# Wedding_Centerpiece_Controller_V1_1.net
KiCad netlist of a schematic drawn in EAGLE
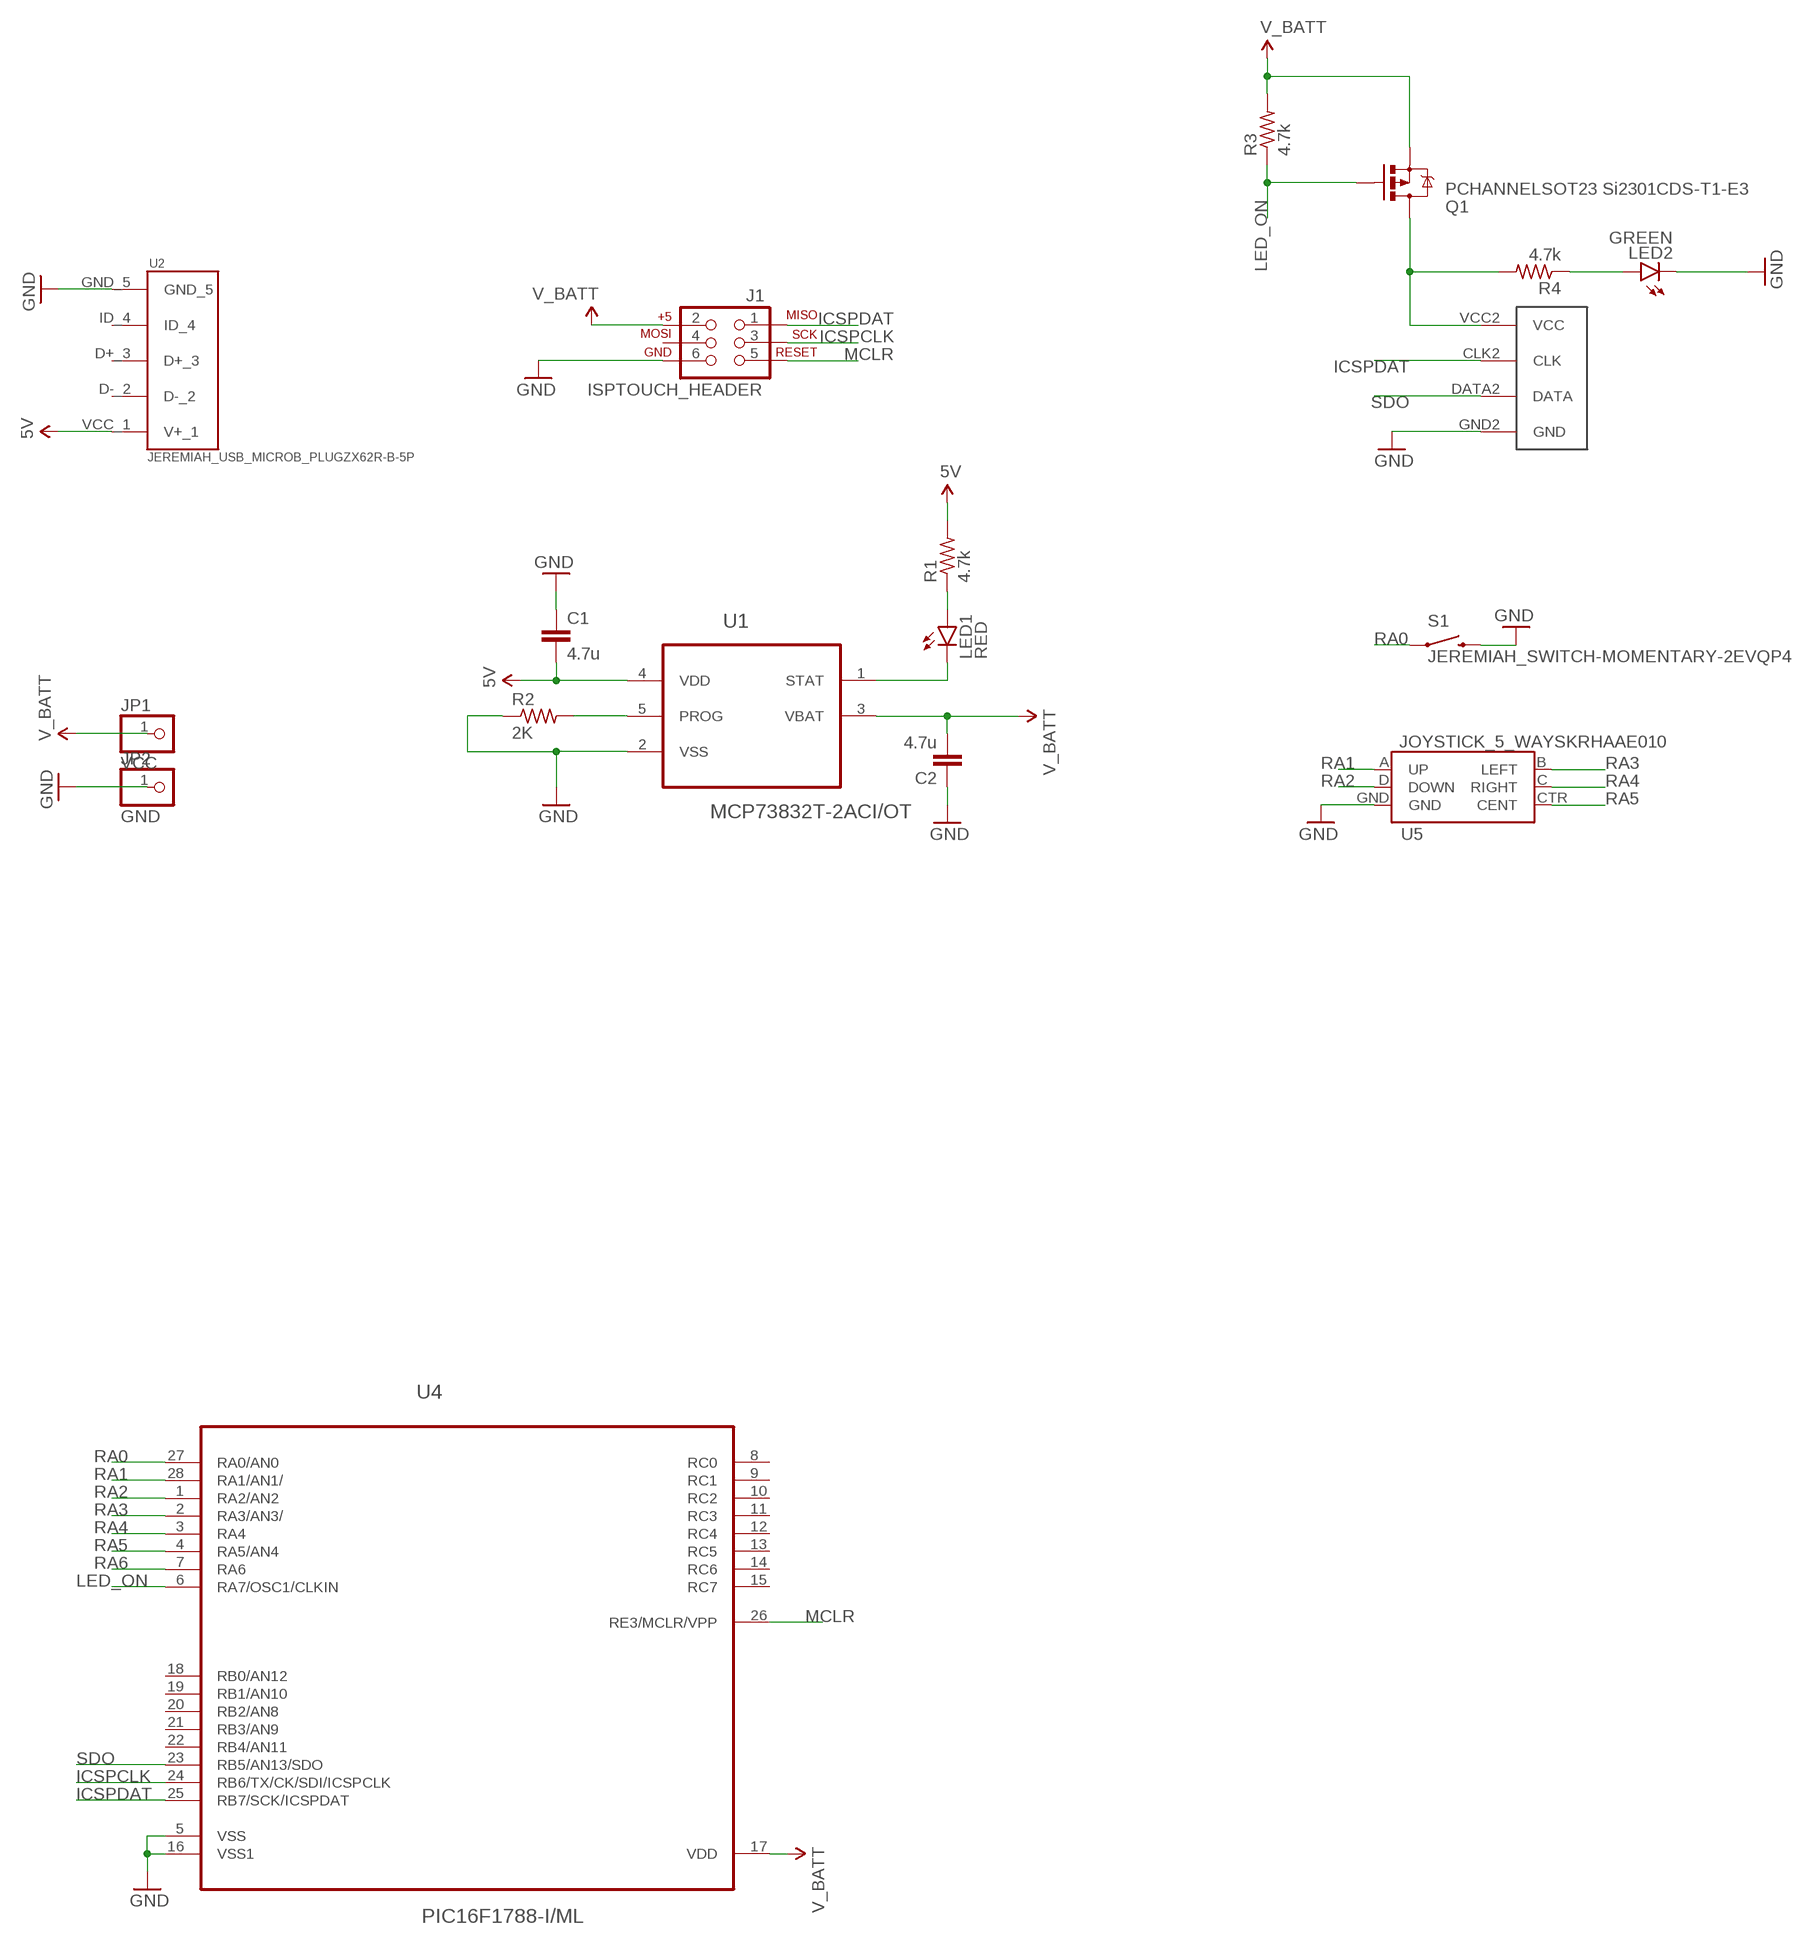
[diagram p0: schematic, sheet 1]

(export (version "E")
  (design (tool "Eeschema 10.0.6"))
  (components
    (comp (ref "C1")
      (value "4.7u")
      (footprint "eagle-import:0402-CAP")
      (libsource (lib "eagle-import") (part "CAP0402-CAP"))
    )
    (comp (ref "C2")
      (value "4.7u")
      (footprint "eagle-import:0402-CAP")
      (libsource (lib "eagle-import") (part "CAP0402-CAP"))
    )
    (comp (ref "J1")
      (value "ISPTOUCH_HEADER")
      (footprint "eagle-import:AVX_9188_6-WAY_MATING_GUIDE")
      (libsource (lib "eagle-import") (part "ISPTOUCH_HEADER"))
    )
    (comp (ref "JP1")
      (value "VCC")
      (footprint "eagle-import:1X01")
      (libsource (lib "eagle-import") (part "PINHD-1X1"))
    )
    (comp (ref "JP2")
      (value "GND")
      (footprint "eagle-import:1X01")
      (libsource (lib "eagle-import") (part "PINHD-1X1"))
    )
    (comp (ref "LED1")
      (value "RED")
      (footprint "eagle-import:LED-0603")
      (libsource (lib "eagle-import") (part "LED0603"))
    )
    (comp (ref "LED2")
      (value "GREEN")
      (footprint "eagle-import:LED-0603")
      (libsource (lib "eagle-import") (part "LED0603"))
    )
    (comp (ref "Q1")
      (value "PCHANNELSOT23 Si2301CDS-T1-E3")
      (footprint "eagle-import:JEREMIAH_SOT23")
      (libsource (lib "eagle-import") (part "JEREMIAH_MOSFET-PCHANNELSOT23"))
    )
    (comp (ref "R1")
      (value "4.7k")
      (footprint "eagle-import:R0402")
      (libsource (lib "eagle-import") (part "R-US_R0402"))
    )
    (comp (ref "R2")
      (value "2K")
      (footprint "eagle-import:R0402")
      (libsource (lib "eagle-import") (part "R-US_R0402"))
    )
    (comp (ref "R3")
      (value "4.7k")
      (footprint "eagle-import:R0402")
      (libsource (lib "eagle-import") (part "R-US_R0402"))
    )
    (comp (ref "R4")
      (value "4.7k")
      (footprint "eagle-import:R0402")
      (libsource (lib "eagle-import") (part "R-US_R0402"))
    )
    (comp (ref "S1")
      (value "JEREMIAH_SWITCH-MOMENTARY-2EVQP4")
      (footprint "eagle-import:JEREMIAH_EVQP4_SWITCH")
      (libsource (lib "eagle-import") (part "JEREMIAH_SWITCH-MOMENTARY-2EVQP4"))
    )
    (comp (ref "U1")
      (value "MCP73832T-2ACI/OT")
      (footprint "eagle-import:SOT95P280X145-5N")
      (libsource (lib "eagle-import") (part "MCP73832T-2ACI/OT"))
    )
    (comp (ref "U2")
      (value "JEREMIAH_USB_MICROB_PLUGZX62R-B-5P")
      (footprint "eagle-import:JEREMIAH_USB_MICRO_ZX62R-B-5P")
      (libsource (lib "eagle-import") (part "JEREMIAH_USB_MICROB_PLUGZX62R-B-5P"))
    )
    (comp (ref "U3")
      (value "JEREMIAH_LED_STRIP_WS2801CLENLED_2L_BEGIN")
      (footprint "eagle-import:JEREMIAH_LED_STRIP_WS2801_CLENLED_2L_BEGIN")
      (libsource (lib "eagle-import") (part "JEREMIAH_LED_STRIP_WS2801CLENLED_2L_BEGIN"))
    )
    (comp (ref "U4")
      (value "PIC16F1788-I/ML")
      (footprint "eagle-import:QFN65P600X600X100-29N")
      (libsource (lib "eagle-import") (part "PIC16F1788-I/ML"))
    )
    (comp (ref "U5")
      (value "JOYSTICK_5_WAYSKRHAAE010")
      (footprint "eagle-import:ALPS_SKRHAAE010")
      (libsource (lib "eagle-import") (part "JOYSTICK_5_WAYSKRHAAE010"))
    )
  )
  (nets
    (net (code "1") (name "/ICSPCLK") (class "Default")
      (node (ref "J1") (pin "3") (pinfunction "3_3") (pintype "passive"))
      (node (ref "U4") (pin "24") (pinfunction "RB6/TX/CK/SDI/ICSPCLK_24") (pintype "bidirectional"))
    )
    (net (code "2") (name "/ICSPDAT") (class "Default")
      (node (ref "J1") (pin "1") (pinfunction "1_1") (pintype "passive"))
      (node (ref "U3") (pin "CLK2") (pinfunction "CLK_CLK2") (pintype "bidirectional"))
      (node (ref "U4") (pin "25") (pinfunction "RB7/SCK/ICSPDAT_25") (pintype "bidirectional"))
    )
    (net (code "3") (name "/LED_ON") (class "Default")
      (node (ref "Q1") (pin "1") (pinfunction "G_1") (pintype "passive"))
      (node (ref "R3") (pin "1") (pinfunction "1_1") (pintype "passive"))
      (node (ref "U4") (pin "6") (pinfunction "RA7/OSC1/CLKIN_6") (pintype "bidirectional"))
    )
    (net (code "4") (name "/MCLR") (class "Default")
      (node (ref "J1") (pin "5") (pinfunction "5_5") (pintype "passive"))
      (node (ref "U4") (pin "26") (pinfunction "RE3/MCLR/VPP_26") (pintype "bidirectional"))
    )
    (net (code "5") (name "/RA0") (class "Default")
      (node (ref "S1") (pin "1") (pinfunction "1_1") (pintype "passive"))
      (node (ref "U4") (pin "27") (pinfunction "RA0/AN0_27") (pintype "bidirectional"))
    )
    (net (code "6") (name "/RA1") (class "Default")
      (node (ref "U4") (pin "28") (pinfunction "RA1/AN1/_28") (pintype "bidirectional"))
      (node (ref "U5") (pin "A") (pinfunction "UP_A") (pintype "bidirectional"))
    )
    (net (code "7") (name "/RA2") (class "Default")
      (node (ref "U4") (pin "1") (pinfunction "RA2/AN2_1") (pintype "bidirectional"))
      (node (ref "U5") (pin "D") (pinfunction "DOWN_D") (pintype "bidirectional"))
    )
    (net (code "8") (name "/RA3") (class "Default")
      (node (ref "U4") (pin "2") (pinfunction "RA3/AN3/_2") (pintype "bidirectional"))
      (node (ref "U5") (pin "B") (pinfunction "LEFT_B") (pintype "bidirectional"))
    )
    (net (code "9") (name "/RA4") (class "Default")
      (node (ref "U4") (pin "3") (pinfunction "RA4_3") (pintype "bidirectional"))
      (node (ref "U5") (pin "C") (pinfunction "RIGHT_C") (pintype "bidirectional"))
    )
    (net (code "10") (name "/RA5") (class "Default")
      (node (ref "U4") (pin "4") (pinfunction "RA5/AN4_4") (pintype "input"))
      (node (ref "U5") (pin "CTR") (pinfunction "CENT_CTR") (pintype "bidirectional"))
    )
    (net (code "11") (name "/RA6") (class "Default")
      (node (ref "U4") (pin "7") (pinfunction "RA6_7") (pintype "bidirectional"))
    )
    (net (code "12") (name "/SDO") (class "Default")
      (node (ref "U3") (pin "DATA2") (pinfunction "DATA_DATA2") (pintype "bidirectional"))
      (node (ref "U4") (pin "23") (pinfunction "RB5/AN13/SDO_23") (pintype "bidirectional"))
    )
    (net (code "13") (name "5V") (class "Default")
      (node (ref "C1") (pin "2") (pinfunction "2_2") (pintype "passive"))
      (node (ref "R1") (pin "2") (pinfunction "2_2") (pintype "passive"))
      (node (ref "U1") (pin "4") (pinfunction "VDD_4") (pintype "power_in"))
      (node (ref "U2") (pin "VCC_1") (pinfunction "V+_1_VCC_1") (pintype "bidirectional"))
    )
    (net (code "14") (name "GND") (class "Default")
      (node (ref "C1") (pin "1") (pinfunction "1_1") (pintype "passive"))
      (node (ref "C2") (pin "1") (pinfunction "1_1") (pintype "passive"))
      (node (ref "J1") (pin "6") (pinfunction "6_6") (pintype "passive"))
      (node (ref "JP2") (pin "1") (pinfunction "1_1") (pintype "passive"))
      (node (ref "LED2") (pin "C") (pinfunction "C_C") (pintype "passive"))
      (node (ref "R2") (pin "1") (pinfunction "1_1") (pintype "passive"))
      (node (ref "S1") (pin "2") (pinfunction "2_2") (pintype "passive"))
      (node (ref "U1") (pin "2") (pinfunction "VSS_2") (pintype "power_in"))
      (node (ref "U2") (pin "GND_5") (pinfunction "GND_5_GND_5") (pintype "bidirectional"))
      (node (ref "U3") (pin "GND2") (pinfunction "GND_GND2") (pintype "bidirectional"))
      (node (ref "U4") (pin "16") (pinfunction "VSS1_16") (pintype "power_in"))
      (node (ref "U4") (pin "5") (pinfunction "VSS_5") (pintype "power_in"))
      (node (ref "U5") (pin "GND") (pinfunction "GND_GND") (pintype "bidirectional"))
    )
    (net (code "15") (name "Net-(LED1-PadA)") (class "Default")
      (node (ref "LED1") (pin "A") (pinfunction "A_A") (pintype "passive"))
      (node (ref "R1") (pin "1") (pinfunction "1_1") (pintype "passive"))
    )
    (net (code "16") (name "Net-(LED2-PadA)") (class "Default")
      (node (ref "LED2") (pin "A") (pinfunction "A_A") (pintype "passive"))
      (node (ref "R4") (pin "1") (pinfunction "1_1") (pintype "passive"))
    )
    (net (code "17") (name "Net-(Q1-D)") (class "Default")
      (node (ref "Q1") (pin "3") (pinfunction "D_3") (pintype "passive"))
      (node (ref "R4") (pin "2") (pinfunction "2_2") (pintype "passive"))
      (node (ref "U3") (pin "VCC2") (pinfunction "VCC_VCC2") (pintype "bidirectional"))
    )
    (net (code "18") (name "Net-(U1-PROG)") (class "Default")
      (node (ref "R2") (pin "2") (pinfunction "2_2") (pintype "passive"))
      (node (ref "U1") (pin "5") (pinfunction "PROG_5") (pintype "input"))
    )
    (net (code "19") (name "Net-(U1-STAT)") (class "Default")
      (node (ref "LED1") (pin "C") (pinfunction "C_C") (pintype "passive"))
      (node (ref "U1") (pin "1") (pinfunction "STAT_1") (pintype "output"))
    )
    (net (code "20") (name "V_BATT") (class "Default")
      (node (ref "C2") (pin "2") (pinfunction "2_2") (pintype "passive"))
      (node (ref "J1") (pin "2") (pinfunction "2_2") (pintype "passive"))
      (node (ref "JP1") (pin "1") (pinfunction "1_1") (pintype "passive"))
      (node (ref "Q1") (pin "2") (pinfunction "S_2") (pintype "passive"))
      (node (ref "R3") (pin "2") (pinfunction "2_2") (pintype "passive"))
      (node (ref "U1") (pin "3") (pinfunction "VBAT_3") (pintype "output"))
      (node (ref "U4") (pin "17") (pinfunction "VDD_17") (pintype "power_in"))
    )
    (net (code "21") (name "unconnected-(J1-Pad4)") (class "Default")
      (node (ref "J1") (pin "4") (pinfunction "4_4") (pintype "passive"))
    )
    (net (code "22") (name "unconnected-(U2-PadD+_3)") (class "Default")
      (node (ref "U2") (pin "D+_3") (pinfunction "D+_3_D+_3") (pintype "bidirectional"))
    )
    (net (code "23") (name "unconnected-(U2-PadD-_2)") (class "Default")
      (node (ref "U2") (pin "D-_2") (pinfunction "D-_2_D-_2") (pintype "bidirectional"))
    )
    (net (code "24") (name "unconnected-(U2-PadID_4)") (class "Default")
      (node (ref "U2") (pin "ID_4") (pinfunction "ID_4_ID_4") (pintype "bidirectional"))
    )
    (net (code "25") (name "unconnected-(U4-RB0{slash}AN12-Pad18)") (class "Default")
      (node (ref "U4") (pin "18") (pinfunction "RB0/AN12_18") (pintype "bidirectional"))
    )
    (net (code "26") (name "unconnected-(U4-RB1{slash}AN10-Pad19)") (class "Default")
      (node (ref "U4") (pin "19") (pinfunction "RB1/AN10_19") (pintype "bidirectional"))
    )
    (net (code "27") (name "unconnected-(U4-RB2{slash}AN8-Pad20)") (class "Default")
      (node (ref "U4") (pin "20") (pinfunction "RB2/AN8_20") (pintype "bidirectional"))
    )
    (net (code "28") (name "unconnected-(U4-RB3{slash}AN9-Pad21)") (class "Default")
      (node (ref "U4") (pin "21") (pinfunction "RB3/AN9_21") (pintype "bidirectional"))
    )
    (net (code "29") (name "unconnected-(U4-RB4{slash}AN11-Pad22)") (class "Default")
      (node (ref "U4") (pin "22") (pinfunction "RB4/AN11_22") (pintype "bidirectional"))
    )
    (net (code "30") (name "unconnected-(U4-RC0-Pad8)") (class "Default")
      (node (ref "U4") (pin "8") (pinfunction "RC0_8") (pintype "bidirectional"))
    )
    (net (code "31") (name "unconnected-(U4-RC1-Pad9)") (class "Default")
      (node (ref "U4") (pin "9") (pinfunction "RC1_9") (pintype "bidirectional"))
    )
    (net (code "32") (name "unconnected-(U4-RC2-Pad10)") (class "Default")
      (node (ref "U4") (pin "10") (pinfunction "RC2_10") (pintype "bidirectional"))
    )
    (net (code "33") (name "unconnected-(U4-RC3-Pad11)") (class "Default")
      (node (ref "U4") (pin "11") (pinfunction "RC3_11") (pintype "bidirectional"))
    )
    (net (code "34") (name "unconnected-(U4-RC4-Pad12)") (class "Default")
      (node (ref "U4") (pin "12") (pinfunction "RC4_12") (pintype "bidirectional"))
    )
    (net (code "35") (name "unconnected-(U4-RC5-Pad13)") (class "Default")
      (node (ref "U4") (pin "13") (pinfunction "RC5_13") (pintype "bidirectional"))
    )
    (net (code "36") (name "unconnected-(U4-RC6-Pad14)") (class "Default")
      (node (ref "U4") (pin "14") (pinfunction "RC6_14") (pintype "bidirectional"))
    )
    (net (code "37") (name "unconnected-(U4-RC7-Pad15)") (class "Default")
      (node (ref "U4") (pin "15") (pinfunction "RC7_15") (pintype "bidirectional"))
    )
  )
)
